# schema.net
KiCad netlist of a schematic drawn in EAGLE
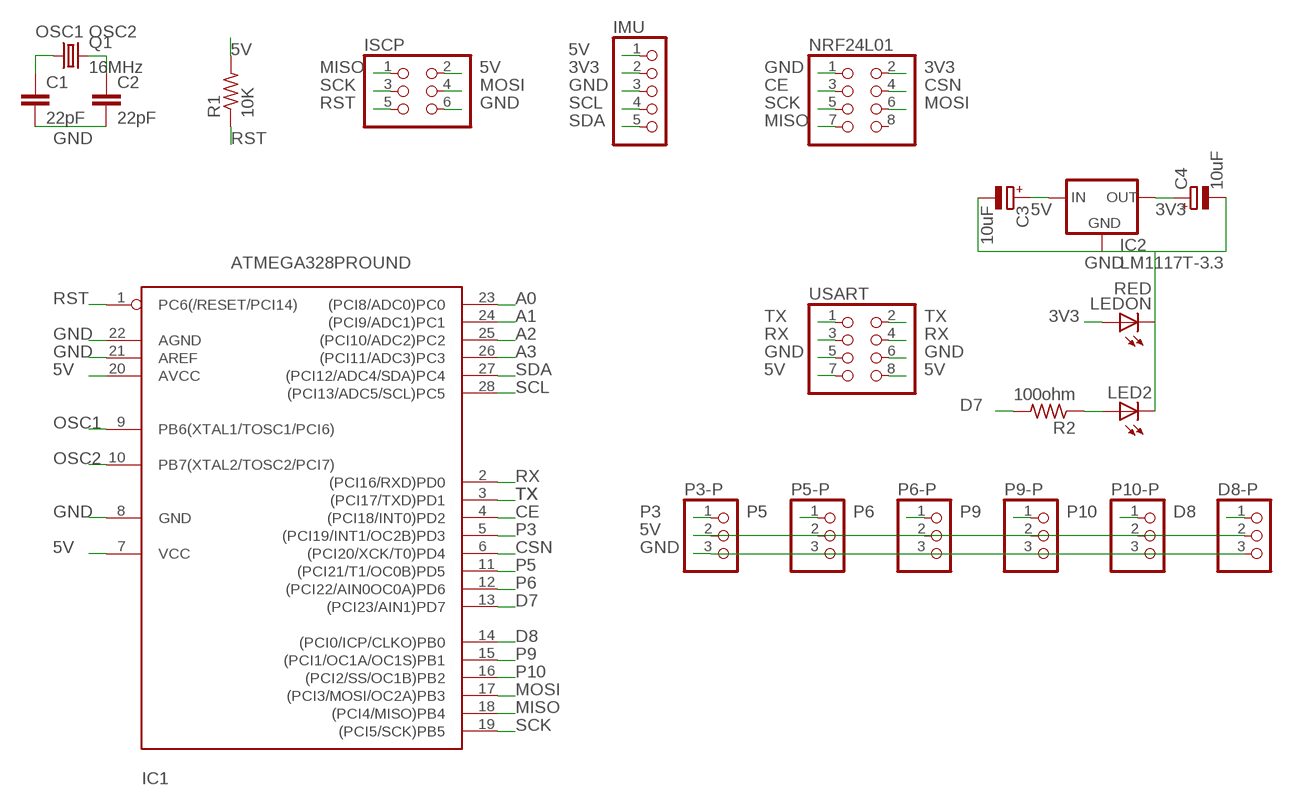
[diagram p0: schematic, sheet 1]

(export (version "E")
  (design (tool "Eeschema 10.0.6"))
  (components
    (comp (ref "C1")
      (value "22pF")
      (footprint "eagle-import:C025-025X050")
      (libsource (lib "eagle-import") (part "C-EU025-025X050"))
    )
    (comp (ref "C2")
      (value "22pF")
      (footprint "eagle-import:C025-025X050")
      (libsource (lib "eagle-import") (part "C-EU025-025X050"))
    )
    (comp (ref "C3")
      (value "10uF")
      (footprint "eagle-import:TT2D5")
      (libsource (lib "eagle-import") (part "CPOL-EUTT2D5"))
    )
    (comp (ref "C4")
      (value "10uF")
      (footprint "eagle-import:TT2D5")
      (libsource (lib "eagle-import") (part "CPOL-EUTT2D5"))
    )
    (comp (ref "D8-P")
      (value "PINHD-1X3")
      (footprint "eagle-import:1X03")
      (libsource (lib "eagle-import") (part "PINHD-1X3"))
    )
    (comp (ref "IC1")
      (value "ATMEGA328PROUND")
      (footprint "eagle-import:DIL28-3-ROUND")
      (libsource (lib "eagle-import") (part "ATMEGA328PROUND"))
    )
    (comp (ref "IC2")
      (value "LM1117T-3.3")
      (footprint "eagle-import:TO220")
      (libsource (lib "eagle-import") (part "LM1117T-3.3"))
    )
    (comp (ref "IMU")
      (value "PINHD-1X5/90")
      (footprint "eagle-import:1X05_90")
      (libsource (lib "eagle-import") (part "PINHD-1X5/90"))
    )
    (comp (ref "ISCP")
      (value "PINHD-2X3")
      (footprint "eagle-import:2X03")
      (libsource (lib "eagle-import") (part "PINHD-2X3"))
    )
    (comp (ref "LED2")
      (value "LED3MM")
      (footprint "eagle-import:LED3MM")
      (libsource (lib "eagle-import") (part "LED3MM"))
    )
    (comp (ref "LEDON")
      (value "RED")
      (footprint "eagle-import:LED3MM")
      (libsource (lib "eagle-import") (part "LED3MM"))
    )
    (comp (ref "NRF24L01")
      (value "PINHD-2X4/90")
      (footprint "eagle-import:2X04_90")
      (libsource (lib "eagle-import") (part "PINHD-2X4/90"))
    )
    (comp (ref "P3-P")
      (value "PINHD-1X3")
      (footprint "eagle-import:1X03")
      (libsource (lib "eagle-import") (part "PINHD-1X3"))
    )
    (comp (ref "P5-P")
      (value "PINHD-1X3")
      (footprint "eagle-import:1X03")
      (libsource (lib "eagle-import") (part "PINHD-1X3"))
    )
    (comp (ref "P6-P")
      (value "PINHD-1X3")
      (footprint "eagle-import:1X03")
      (libsource (lib "eagle-import") (part "PINHD-1X3"))
    )
    (comp (ref "P9-P")
      (value "PINHD-1X3")
      (footprint "eagle-import:1X03")
      (libsource (lib "eagle-import") (part "PINHD-1X3"))
    )
    (comp (ref "P10-P")
      (value "PINHD-1X3")
      (footprint "eagle-import:1X03")
      (libsource (lib "eagle-import") (part "PINHD-1X3"))
    )
    (comp (ref "Q1")
      (value "16MHz")
      (footprint "eagle-import:HC49U70")
      (libsource (lib "eagle-import") (part "CRYSTALHC49U70"))
    )
    (comp (ref "R1")
      (value "10K")
      (footprint "eagle-import:0207_12")
      (libsource (lib "eagle-import") (part "R-US_0207/12"))
    )
    (comp (ref "R2")
      (value "100ohm")
      (footprint "eagle-import:0207_12")
      (libsource (lib "eagle-import") (part "R-US_0207/12"))
    )
    (comp (ref "USART")
      (value "PINHD-2X4")
      (footprint "eagle-import:2X04")
      (libsource (lib "eagle-import") (part "PINHD-2X4"))
    )
  )
  (nets
    (net (code "1") (name "/3V3") (class "Default")
      (node (ref "C4") (pin "+") (pinfunction "+_+") (pintype "passive"))
      (node (ref "IC2") (pin "2") (pinfunction "OUT_2") (pintype "passive"))
      (node (ref "IMU") (pin "2") (pinfunction "2_2") (pintype "passive"))
      (node (ref "LEDON") (pin "A") (pinfunction "A_A") (pintype "passive"))
      (node (ref "NRF24L01") (pin "2") (pinfunction "2_2") (pintype "passive"))
    )
    (net (code "2") (name "/5V") (class "Default")
      (node (ref "C3") (pin "+") (pinfunction "+_+") (pintype "passive"))
      (node (ref "D8-P") (pin "2") (pinfunction "2_2") (pintype "passive"))
      (node (ref "IC1") (pin "20") (pinfunction "AVCC_20") (pintype "bidirectional"))
      (node (ref "IC1") (pin "7") (pinfunction "VCC_7") (pintype "bidirectional"))
      (node (ref "IC2") (pin "3") (pinfunction "IN_3") (pintype "input"))
      (node (ref "IMU") (pin "1") (pinfunction "1_1") (pintype "passive"))
      (node (ref "ISCP") (pin "2") (pinfunction "2_2") (pintype "passive"))
      (node (ref "P10-P") (pin "2") (pinfunction "2_2") (pintype "passive"))
      (node (ref "P3-P") (pin "2") (pinfunction "2_2") (pintype "passive"))
      (node (ref "P5-P") (pin "2") (pinfunction "2_2") (pintype "passive"))
      (node (ref "P6-P") (pin "2") (pinfunction "2_2") (pintype "passive"))
      (node (ref "P9-P") (pin "2") (pinfunction "2_2") (pintype "passive"))
      (node (ref "R1") (pin "2") (pinfunction "2_2") (pintype "passive"))
      (node (ref "USART") (pin "7") (pinfunction "7_7") (pintype "passive"))
      (node (ref "USART") (pin "8") (pinfunction "8_8") (pintype "passive"))
    )
    (net (code "3") (name "/A0") (class "Default")
      (node (ref "IC1") (pin "23") (pinfunction "(PCI8/ADC0)PC0_23") (pintype "bidirectional"))
    )
    (net (code "4") (name "/A1") (class "Default")
      (node (ref "IC1") (pin "24") (pinfunction "(PCI9/ADC1)PC1_24") (pintype "bidirectional"))
    )
    (net (code "5") (name "/A2") (class "Default")
      (node (ref "IC1") (pin "25") (pinfunction "(PCI10/ADC2)PC2_25") (pintype "bidirectional"))
    )
    (net (code "6") (name "/A3") (class "Default")
      (node (ref "IC1") (pin "26") (pinfunction "(PCI11/ADC3)PC3_26") (pintype "bidirectional"))
    )
    (net (code "7") (name "/CE") (class "Default")
      (node (ref "IC1") (pin "4") (pinfunction "(PCI18/INT0)PD2_4") (pintype "bidirectional"))
      (node (ref "NRF24L01") (pin "3") (pinfunction "3_3") (pintype "passive"))
    )
    (net (code "8") (name "/CSN") (class "Default")
      (node (ref "IC1") (pin "6") (pinfunction "(PCI20/XCK/T0)PD4_6") (pintype "bidirectional"))
      (node (ref "NRF24L01") (pin "4") (pinfunction "4_4") (pintype "passive"))
    )
    (net (code "9") (name "/D7") (class "Default")
      (node (ref "IC1") (pin "13") (pinfunction "(PCI23/AIN1)PD7_13") (pintype "bidirectional"))
      (node (ref "R2") (pin "2") (pinfunction "2_2") (pintype "passive"))
    )
    (net (code "10") (name "/D8") (class "Default")
      (node (ref "D8-P") (pin "1") (pinfunction "1_1") (pintype "passive"))
      (node (ref "IC1") (pin "14") (pinfunction "(PCI0/ICP/CLKO)PB0_14") (pintype "bidirectional"))
    )
    (net (code "11") (name "/GND") (class "Default")
      (node (ref "C1") (pin "2") (pinfunction "2_2") (pintype "passive"))
      (node (ref "C2") (pin "2") (pinfunction "2_2") (pintype "passive"))
      (node (ref "C3") (pin "-") (pinfunction "-_-") (pintype "passive"))
      (node (ref "C4") (pin "-") (pinfunction "-_-") (pintype "passive"))
      (node (ref "D8-P") (pin "3") (pinfunction "3_3") (pintype "passive"))
      (node (ref "IC1") (pin "21") (pinfunction "AREF_21") (pintype "bidirectional"))
      (node (ref "IC1") (pin "22") (pinfunction "AGND_22") (pintype "bidirectional"))
      (node (ref "IC1") (pin "8") (pinfunction "GND_8") (pintype "bidirectional"))
      (node (ref "IC2") (pin "1") (pinfunction "GND_1") (pintype "input"))
      (node (ref "IMU") (pin "3") (pinfunction "3_3") (pintype "passive"))
      (node (ref "ISCP") (pin "6") (pinfunction "6_6") (pintype "passive"))
      (node (ref "LED2") (pin "K") (pinfunction "C_K") (pintype "passive"))
      (node (ref "LEDON") (pin "K") (pinfunction "C_K") (pintype "passive"))
      (node (ref "NRF24L01") (pin "1") (pinfunction "1_1") (pintype "passive"))
      (node (ref "P10-P") (pin "3") (pinfunction "3_3") (pintype "passive"))
      (node (ref "P3-P") (pin "3") (pinfunction "3_3") (pintype "passive"))
      (node (ref "P5-P") (pin "3") (pinfunction "3_3") (pintype "passive"))
      (node (ref "P6-P") (pin "3") (pinfunction "3_3") (pintype "passive"))
      (node (ref "P9-P") (pin "3") (pinfunction "3_3") (pintype "passive"))
      (node (ref "USART") (pin "5") (pinfunction "5_5") (pintype "passive"))
      (node (ref "USART") (pin "6") (pinfunction "6_6") (pintype "passive"))
    )
    (net (code "12") (name "/MISO") (class "Default")
      (node (ref "IC1") (pin "18") (pinfunction "(PCI4/MISO)PB4_18") (pintype "bidirectional"))
      (node (ref "ISCP") (pin "1") (pinfunction "1_1") (pintype "passive"))
      (node (ref "NRF24L01") (pin "7") (pinfunction "7_7") (pintype "passive"))
    )
    (net (code "13") (name "/MOSI") (class "Default")
      (node (ref "IC1") (pin "17") (pinfunction "(PCI3/MOSI/OC2A)PB3_17") (pintype "bidirectional"))
      (node (ref "ISCP") (pin "4") (pinfunction "4_4") (pintype "passive"))
      (node (ref "NRF24L01") (pin "6") (pinfunction "6_6") (pintype "passive"))
    )
    (net (code "14") (name "/OSC1") (class "Default")
      (node (ref "C1") (pin "1") (pinfunction "1_1") (pintype "passive"))
      (node (ref "IC1") (pin "9") (pinfunction "PB6(XTAL1/TOSC1/PCI6)_9") (pintype "bidirectional"))
      (node (ref "Q1") (pin "1") (pinfunction "1_1") (pintype "passive"))
    )
    (net (code "15") (name "/OSC2") (class "Default")
      (node (ref "C2") (pin "1") (pinfunction "1_1") (pintype "passive"))
      (node (ref "IC1") (pin "10") (pinfunction "PB7(XTAL2/TOSC2/PCI7)_10") (pintype "bidirectional"))
      (node (ref "Q1") (pin "2") (pinfunction "2_2") (pintype "passive"))
    )
    (net (code "16") (name "/P3") (class "Default")
      (node (ref "IC1") (pin "5") (pinfunction "(PCI19/INT1/OC2B)PD3_5") (pintype "bidirectional"))
      (node (ref "P3-P") (pin "1") (pinfunction "1_1") (pintype "passive"))
    )
    (net (code "17") (name "/P5") (class "Default")
      (node (ref "IC1") (pin "11") (pinfunction "(PCI21/T1/OC0B)PD5_11") (pintype "bidirectional"))
      (node (ref "P5-P") (pin "1") (pinfunction "1_1") (pintype "passive"))
    )
    (net (code "18") (name "/P6") (class "Default")
      (node (ref "IC1") (pin "12") (pinfunction "(PCI22/AIN0OC0A)PD6_12") (pintype "bidirectional"))
      (node (ref "P6-P") (pin "1") (pinfunction "1_1") (pintype "passive"))
    )
    (net (code "19") (name "/P9") (class "Default")
      (node (ref "IC1") (pin "15") (pinfunction "(PCI1/OC1A/OC1S)PB1_15") (pintype "bidirectional"))
      (node (ref "P9-P") (pin "1") (pinfunction "1_1") (pintype "passive"))
    )
    (net (code "20") (name "/P10") (class "Default")
      (node (ref "IC1") (pin "16") (pinfunction "(PCI2/SS/OC1B)PB2_16") (pintype "bidirectional"))
      (node (ref "P10-P") (pin "1") (pinfunction "1_1") (pintype "passive"))
    )
    (net (code "21") (name "/RST") (class "Default")
      (node (ref "IC1") (pin "1") (pinfunction "PC6(/RESET/PCI14)_1") (pintype "bidirectional"))
      (node (ref "ISCP") (pin "5") (pinfunction "5_5") (pintype "passive"))
      (node (ref "R1") (pin "1") (pinfunction "1_1") (pintype "passive"))
    )
    (net (code "22") (name "/RX") (class "Default")
      (node (ref "IC1") (pin "2") (pinfunction "(PCI16/RXD)PD0_2") (pintype "bidirectional"))
      (node (ref "USART") (pin "3") (pinfunction "3_3") (pintype "passive"))
      (node (ref "USART") (pin "4") (pinfunction "4_4") (pintype "passive"))
    )
    (net (code "23") (name "/SCK") (class "Default")
      (node (ref "IC1") (pin "19") (pinfunction "(PCI5/SCK)PB5_19") (pintype "bidirectional"))
      (node (ref "ISCP") (pin "3") (pinfunction "3_3") (pintype "passive"))
      (node (ref "NRF24L01") (pin "5") (pinfunction "5_5") (pintype "passive"))
    )
    (net (code "24") (name "/SCL") (class "Default")
      (node (ref "IC1") (pin "28") (pinfunction "(PCI13/ADC5/SCL)PC5_28") (pintype "bidirectional"))
      (node (ref "IMU") (pin "4") (pinfunction "4_4") (pintype "passive"))
    )
    (net (code "25") (name "/SDA") (class "Default")
      (node (ref "IC1") (pin "27") (pinfunction "(PCI12/ADC4/SDA)PC4_27") (pintype "bidirectional"))
      (node (ref "IMU") (pin "5") (pinfunction "5_5") (pintype "passive"))
    )
    (net (code "26") (name "/TX") (class "Default")
      (node (ref "IC1") (pin "3") (pinfunction "(PCI17/TXD)PD1_3") (pintype "bidirectional"))
      (node (ref "USART") (pin "1") (pinfunction "1_1") (pintype "passive"))
      (node (ref "USART") (pin "2") (pinfunction "2_2") (pintype "passive"))
    )
    (net (code "27") (name "Net-(LED2-PadA)") (class "Default")
      (node (ref "LED2") (pin "A") (pinfunction "A_A") (pintype "passive"))
      (node (ref "R2") (pin "1") (pinfunction "1_1") (pintype "passive"))
    )
    (net (code "28") (name "unconnected-(NRF24L01-Pad8)") (class "Default")
      (node (ref "NRF24L01") (pin "8") (pinfunction "8_8") (pintype "passive"))
    )
  )
)
